# LCD.net
KiCad netlist of a schematic drawn in Altium Designer
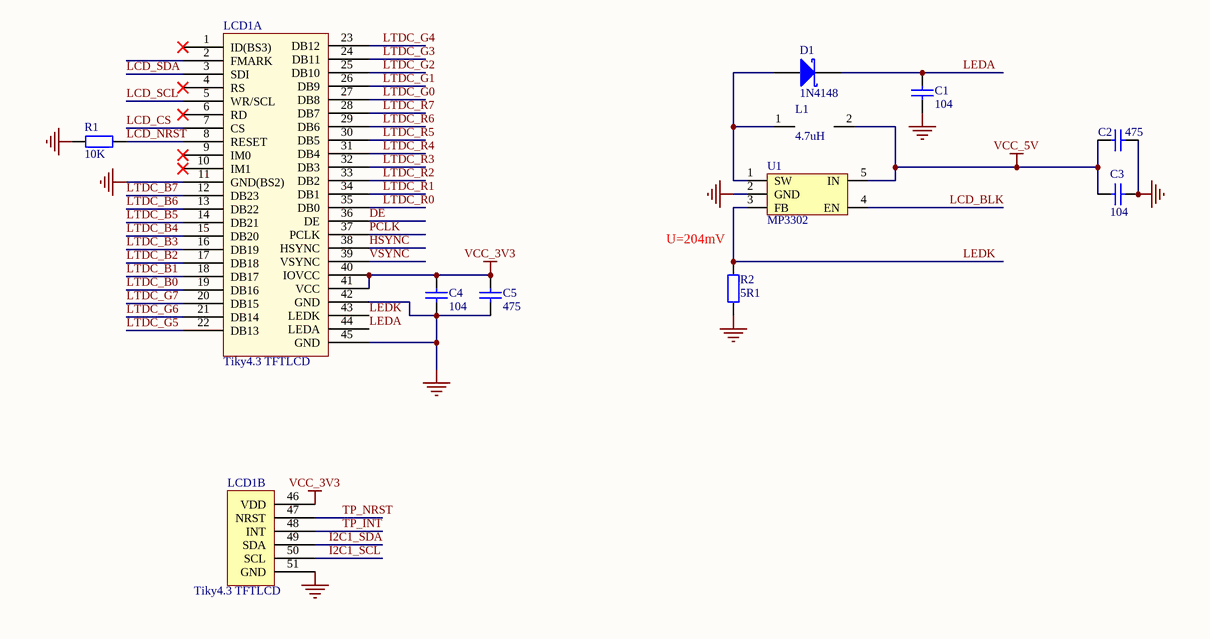
[diagram p0: LCD.SchDoc]

(export (version "E")
  (design (tool "Eeschema 10.0.6"))
  (components
    (comp (ref "C1")
      (value "104")
      (footprint "C0402_M")
      (description "贴片电容/MLCC电容")
      (libsource (lib "0.1 - 电阻-电容-电感-晶振-晶体-磁珠-电位器-法拉电容-馈通电容") (part "C"))
    )
    (comp (ref "C2")
      (value "475")
      (footprint "C0402_M")
      (description "贴片电容/MLCC电容")
      (libsource (lib "0.1 - 电阻-电容-电感-晶振-晶体-磁珠-电位器-法拉电容-馈通电容") (part "C"))
    )
    (comp (ref "C3")
      (value "104")
      (footprint "C0402_M")
      (description "贴片电容/MLCC电容")
      (libsource (lib "0.1 - 电阻-电容-电感-晶振-晶体-磁珠-电位器-法拉电容-馈通电容") (part "C"))
    )
    (comp (ref "C4")
      (value "104")
      (footprint "C0402_M")
      (description "贴片电容/MLCC电容")
      (libsource (lib "0.1 - 电阻-电容-电感-晶振-晶体-磁珠-电位器-法拉电容-馈通电容") (part "C"))
    )
    (comp (ref "C5")
      (value "475")
      (footprint "C0402_M")
      (description "贴片电容/MLCC电容")
      (libsource (lib "0.1 - 电阻-电容-电感-晶振-晶体-磁珠-电位器-法拉电容-馈通电容") (part "C"))
    )
    (comp (ref "D1")
      (value "1N4148")
      (footprint "SOD-123")
      (description "Schottky Diode")
      (fields (field (name "PUBLISHER") "Altium Limited"))
      (libsource (lib "Miscellaneous Devices") (part "D Schottky"))
    )
    (comp (ref "L1") (value "4.7uH") (footprint "L1206") (libsource (lib "Tiky") (part "Inductor")))
    (comp (ref "LCD1")
      (value "Tiky4.3 TFTLCD")
      (footprint "Tiky 4.3 TFTLCD")
      (libsource (lib "MySchlib") (part "Tiky4.3 TFTLCD"))
    )
    (comp (ref "R1")
      (value "10K")
      (footprint "R0402_M")
      (description "贴片电阻")
      (libsource (lib "0.1 - 电阻-电容-电感-晶振-晶体-磁珠-电位器-法拉电容-馈通电容") (part "R"))
    )
    (comp (ref "R2")
      (value "5R1")
      (footprint "R0603_M")
      (description "贴片电阻")
      (libsource (lib "0.1 - 电阻-电容-电感-晶振-晶体-磁珠-电位器-法拉电容-馈通电容") (part "R"))
    )
    (comp (ref "U1") (value "MP3302") (footprint "SOT23-5") (libsource (lib "Tiky") (part "MP3302")))
  )
  (nets
    (net (code "1") (name "/DE") (class "Default")
      (node (ref "LCD1") (pin "36") (pinfunction "DE_36") (pintype "passive"))
    )
    (net (code "2") (name "/HSYNC") (class "Default")
      (node (ref "LCD1") (pin "38") (pinfunction "HSYNC_38") (pintype "passive"))
    )
    (net (code "3") (name "/I2C1_SCL") (class "Default")
      (node (ref "LCD1") (pin "50") (pinfunction "SCL_50") (pintype "passive"))
    )
    (net (code "4") (name "/I2C1_SDA") (class "Default")
      (node (ref "LCD1") (pin "49") (pinfunction "SDA_49") (pintype "passive"))
    )
    (net (code "5") (name "/LCD_BLK") (class "Default")
      (node (ref "U1") (pin "4") (pinfunction "EN_4") (pintype "passive"))
    )
    (net (code "6") (name "/LCD_CS") (class "Default")
      (node (ref "LCD1") (pin "7") (pinfunction "CS_7") (pintype "passive"))
    )
    (net (code "7") (name "/LCD_NRST") (class "Default")
      (node (ref "LCD1") (pin "8") (pinfunction "RESET_8") (pintype "passive"))
      (node (ref "R1") (pin "2") (pinfunction "2_2") (pintype "passive"))
    )
    (net (code "8") (name "/LCD_SCL") (class "Default")
      (node (ref "LCD1") (pin "5") (pinfunction "WR/SCL_5") (pintype "passive"))
    )
    (net (code "9") (name "/LCD_SDA") (class "Default")
      (node (ref "LCD1") (pin "3") (pinfunction "SDI_3") (pintype "passive"))
    )
    (net (code "10") (name "/LEDA") (class "Default")
      (node (ref "C1") (pin "1") (pinfunction "1_1") (pintype "passive"))
      (node (ref "D1") (pin "2") (pinfunction "K_2") (pintype "passive"))
      (node (ref "LCD1") (pin "44") (pinfunction "LEDA_44") (pintype "passive"))
    )
    (net (code "11") (name "/LEDK") (class "Default")
      (node (ref "LCD1") (pin "43") (pinfunction "LEDK_43") (pintype "passive"))
      (node (ref "R2") (pin "1") (pinfunction "1_1") (pintype "passive"))
      (node (ref "U1") (pin "3") (pinfunction "FB_3") (pintype "passive"))
    )
    (net (code "12") (name "/LTDC_B0") (class "Default")
      (node (ref "LCD1") (pin "19") (pinfunction "DB16_19") (pintype "passive"))
    )
    (net (code "13") (name "/LTDC_B1") (class "Default")
      (node (ref "LCD1") (pin "18") (pinfunction "DB17_18") (pintype "passive"))
    )
    (net (code "14") (name "/LTDC_B2") (class "Default")
      (node (ref "LCD1") (pin "17") (pinfunction "DB18_17") (pintype "passive"))
    )
    (net (code "15") (name "/LTDC_B3") (class "Default")
      (node (ref "LCD1") (pin "16") (pinfunction "DB19_16") (pintype "passive"))
    )
    (net (code "16") (name "/LTDC_B4") (class "Default")
      (node (ref "LCD1") (pin "15") (pinfunction "DB20_15") (pintype "passive"))
    )
    (net (code "17") (name "/LTDC_B5") (class "Default")
      (node (ref "LCD1") (pin "14") (pinfunction "DB21_14") (pintype "passive"))
    )
    (net (code "18") (name "/LTDC_B6") (class "Default")
      (node (ref "LCD1") (pin "13") (pinfunction "DB22_13") (pintype "passive"))
    )
    (net (code "19") (name "/LTDC_B7") (class "Default")
      (node (ref "LCD1") (pin "12") (pinfunction "DB23_12") (pintype "passive"))
    )
    (net (code "20") (name "/LTDC_G0") (class "Default")
      (node (ref "LCD1") (pin "27") (pinfunction "DB8_27") (pintype "passive"))
    )
    (net (code "21") (name "/LTDC_G1") (class "Default")
      (node (ref "LCD1") (pin "26") (pinfunction "DB9_26") (pintype "passive"))
    )
    (net (code "22") (name "/LTDC_G2") (class "Default")
      (node (ref "LCD1") (pin "25") (pinfunction "DB10_25") (pintype "passive"))
    )
    (net (code "23") (name "/LTDC_G3") (class "Default")
      (node (ref "LCD1") (pin "24") (pinfunction "DB11_24") (pintype "passive"))
    )
    (net (code "24") (name "/LTDC_G4") (class "Default")
      (node (ref "LCD1") (pin "23") (pinfunction "DB12_23") (pintype "passive"))
    )
    (net (code "25") (name "/LTDC_G5") (class "Default")
      (node (ref "LCD1") (pin "22") (pinfunction "DB13_22") (pintype "passive"))
    )
    (net (code "26") (name "/LTDC_G6") (class "Default")
      (node (ref "LCD1") (pin "21") (pinfunction "DB14_21") (pintype "passive"))
    )
    (net (code "27") (name "/LTDC_G7") (class "Default")
      (node (ref "LCD1") (pin "20") (pinfunction "DB15_20") (pintype "passive"))
    )
    (net (code "28") (name "/LTDC_R0") (class "Default")
      (node (ref "LCD1") (pin "35") (pinfunction "DB0_35") (pintype "passive"))
    )
    (net (code "29") (name "/LTDC_R1") (class "Default")
      (node (ref "LCD1") (pin "34") (pinfunction "DB1_34") (pintype "passive"))
    )
    (net (code "30") (name "/LTDC_R2") (class "Default")
      (node (ref "LCD1") (pin "33") (pinfunction "DB2_33") (pintype "passive"))
    )
    (net (code "31") (name "/LTDC_R3") (class "Default")
      (node (ref "LCD1") (pin "32") (pinfunction "DB3_32") (pintype "passive"))
    )
    (net (code "32") (name "/LTDC_R4") (class "Default")
      (node (ref "LCD1") (pin "31") (pinfunction "DB4_31") (pintype "passive"))
    )
    (net (code "33") (name "/LTDC_R5") (class "Default")
      (node (ref "LCD1") (pin "30") (pinfunction "DB5_30") (pintype "passive"))
    )
    (net (code "34") (name "/LTDC_R6") (class "Default")
      (node (ref "LCD1") (pin "29") (pinfunction "DB6_29") (pintype "passive"))
    )
    (net (code "35") (name "/LTDC_R7") (class "Default")
      (node (ref "LCD1") (pin "28") (pinfunction "DB7_28") (pintype "passive"))
    )
    (net (code "36") (name "/PCLK") (class "Default")
      (node (ref "LCD1") (pin "37") (pinfunction "PCLK_37") (pintype "passive"))
    )
    (net (code "37") (name "/TP_INT") (class "Default")
      (node (ref "LCD1") (pin "48") (pinfunction "INT_48") (pintype "passive"))
    )
    (net (code "38") (name "/TP_NRST") (class "Default")
      (node (ref "LCD1") (pin "47") (pinfunction "NRST_47") (pintype "passive"))
    )
    (net (code "39") (name "/VSYNC") (class "Default")
      (node (ref "LCD1") (pin "39") (pinfunction "VSYNC_39") (pintype "passive"))
    )
    (net (code "40") (name "GND") (class "Default")
      (node (ref "C1") (pin "2") (pinfunction "2_2") (pintype "passive"))
      (node (ref "C2") (pin "1") (pinfunction "1_1") (pintype "passive"))
      (node (ref "C3") (pin "2") (pinfunction "2_2") (pintype "passive"))
      (node (ref "C4") (pin "2") (pinfunction "2_2") (pintype "passive"))
      (node (ref "C5") (pin "2") (pinfunction "2_2") (pintype "passive"))
      (node (ref "LCD1") (pin "11") (pinfunction "GND(BS2)_11") (pintype "passive"))
      (node (ref "LCD1") (pin "42") (pinfunction "GND_42") (pintype "passive"))
      (node (ref "LCD1") (pin "45") (pinfunction "GND_45") (pintype "passive"))
      (node (ref "LCD1") (pin "51") (pinfunction "GND_51") (pintype "passive"))
      (node (ref "R1") (pin "1") (pinfunction "1_1") (pintype "passive"))
      (node (ref "R2") (pin "2") (pinfunction "2_2") (pintype "passive"))
      (node (ref "U1") (pin "2") (pinfunction "GND_2") (pintype "passive"))
    )
    (net (code "41") (name "Net-(D1-A)") (class "Default")
      (node (ref "D1") (pin "1") (pinfunction "A_1") (pintype "passive"))
      (node (ref "L1") (pin "1") (pinfunction "1_1") (pintype "passive"))
      (node (ref "U1") (pin "1") (pinfunction "SW_1") (pintype "passive"))
    )
    (net (code "42") (name "VCC_3V3") (class "Default")
      (node (ref "C4") (pin "1") (pinfunction "1_1") (pintype "passive"))
      (node (ref "C5") (pin "1") (pinfunction "1_1") (pintype "passive"))
      (node (ref "LCD1") (pin "40") (pinfunction "IOVCC_40") (pintype "passive"))
      (node (ref "LCD1") (pin "41") (pinfunction "VCC_41") (pintype "passive"))
      (node (ref "LCD1") (pin "46") (pinfunction "VDD_46") (pintype "passive"))
    )
    (net (code "43") (name "VCC_5V") (class "Default")
      (node (ref "C2") (pin "2") (pinfunction "2_2") (pintype "passive"))
      (node (ref "C3") (pin "1") (pinfunction "1_1") (pintype "passive"))
      (node (ref "L1") (pin "2") (pinfunction "2_2") (pintype "passive"))
      (node (ref "U1") (pin "5") (pinfunction "IN_5") (pintype "passive"))
    )
    (net (code "44") (name "unconnected-(LCD1A-FMARK-Pad2)") (class "Default")
      (node (ref "LCD1") (pin "2") (pinfunction "FMARK_2") (pintype "passive"))
    )
    (net (code "45") (name "unconnected-(LCD1A-ID(BS3)-Pad1)") (class "Default")
      (node (ref "LCD1") (pin "1") (pinfunction "ID(BS3)_1") (pintype "passive+no_connect"))
    )
    (net (code "46") (name "unconnected-(LCD1A-IM0-Pad9)") (class "Default")
      (node (ref "LCD1") (pin "9") (pinfunction "IM0_9") (pintype "passive+no_connect"))
    )
    (net (code "47") (name "unconnected-(LCD1A-IM1-Pad10)") (class "Default")
      (node (ref "LCD1") (pin "10") (pinfunction "IM1_10") (pintype "passive+no_connect"))
    )
    (net (code "48") (name "unconnected-(LCD1A-RD-Pad6)") (class "Default")
      (node (ref "LCD1") (pin "6") (pinfunction "RD_6") (pintype "passive+no_connect"))
    )
    (net (code "49") (name "unconnected-(LCD1A-RS-Pad4)") (class "Default")
      (node (ref "LCD1") (pin "4") (pinfunction "RS_4") (pintype "passive+no_connect"))
    )
  )
)
